# ble_lock_2020-10-10.net
KiCad netlist of a schematic drawn in Altium Designer
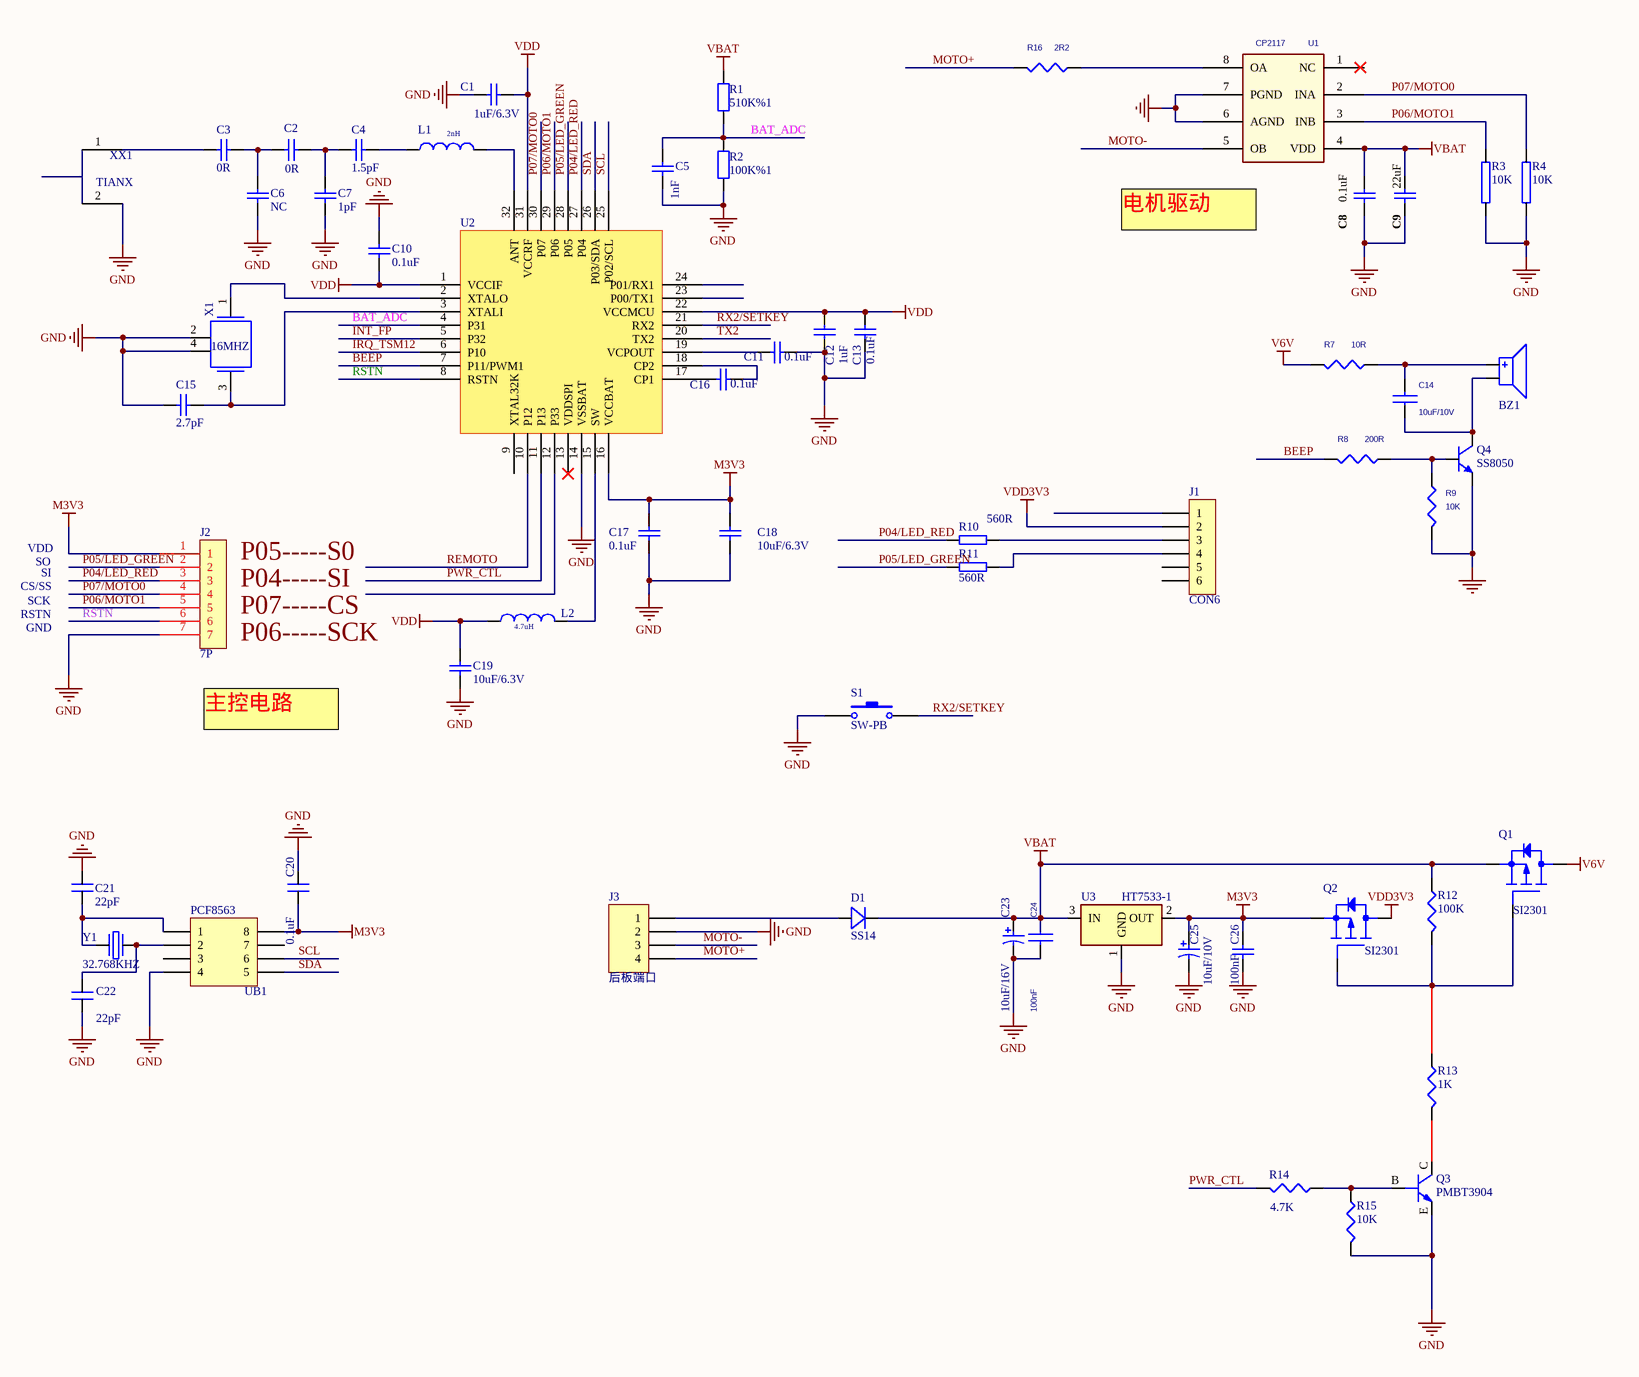
[diagram p0: ble_lock_2020-10-10.SchDoc]

(export (version "E")
  (design (tool "Eeschema 10.0.6"))
  (components
    (comp (ref "BZ1")
      (value "BUZZER")
      (footprint "BUZZER_D93_L40")
      (description "Buzzer")
      (libsource (lib "MyLibrary") (part "BUZZER"))
    )
    (comp (ref "C1")
      (value "1uF/6.3V")
      (footprint "0603C")
      (description "Capacitor")
      (fields (field (name "PUBLISHER") "Altium Limited"))
      (libsource (lib "MySchlib") (part "Cap"))
    )
    (comp (ref "C2")
      (value "0R")
      (footprint "0603C")
      (description "Capacitor")
      (fields (field (name "PUBLISHER") "Altium Limited"))
      (libsource (lib "MySchlib") (part "Cap"))
    )
    (comp (ref "C3")
      (value "0R")
      (footprint "0603C")
      (description "Capacitor")
      (fields (field (name "PUBLISHER") "Altium Limited"))
      (libsource (lib "MySchlib") (part "Cap"))
    )
    (comp (ref "C4")
      (value "1.5pF")
      (footprint "0603C")
      (description "Capacitor")
      (fields (field (name "PUBLISHER") "Altium Limited"))
      (libsource (lib "MySchlib") (part "Cap"))
    )
    (comp (ref "C5")
      (value "1nF")
      (footprint "0603C")
      (description "Capacitor, Ceramic")
      (fields (field (name "TOLERANCE") "5 %"))
      (libsource (lib "MyLibrary") (part "CAP-NP"))
    )
    (comp (ref "C6")
      (value "NC")
      (footprint "0603C")
      (description "Capacitor")
      (fields (field (name "PUBLISHER") "Altium Limited"))
      (libsource (lib "MySchlib") (part "Cap"))
    )
    (comp (ref "C7")
      (value "1pF")
      (footprint "0603C")
      (description "Capacitor")
      (fields (field (name "PUBLISHER") "Altium Limited"))
      (libsource (lib "MySchlib") (part "Cap"))
    )
    (comp (ref "C8")
      (value "0.1uF")
      (footprint "0603C")
      (description "Capacitor, Ceramic")
      (fields (field (name "TOLERANCE") "5 %"))
      (libsource (lib "MyLibrary") (part "CAP-NP"))
    )
    (comp (ref "C9")
      (value "22uF")
      (footprint "0805C")
      (description "Capacitor, Ceramic")
      (fields (field (name "TOLERANCE") "5 %"))
      (libsource (lib "MyLibrary") (part "CAP-NP"))
    )
    (comp (ref "C10")
      (value "0.1uF")
      (footprint "0603C")
      (description "Capacitor")
      (fields (field (name "PUBLISHER") "Altium Limited"))
      (libsource (lib "MySchlib") (part "Cap"))
    )
    (comp (ref "C11")
      (value "0.1uF")
      (footprint "0603C")
      (description "Capacitor")
      (fields (field (name "PUBLISHER") "Altium Limited"))
      (libsource (lib "MySchlib") (part "Cap"))
    )
    (comp (ref "C12")
      (value "1uF")
      (footprint "0603C")
      (description "Capacitor")
      (fields (field (name "PUBLISHER") "Altium Limited"))
      (libsource (lib "MySchlib") (part "Cap"))
    )
    (comp (ref "C13")
      (value "0.1uF")
      (footprint "0603C")
      (description "Capacitor")
      (fields (field (name "PUBLISHER") "Altium Limited"))
      (libsource (lib "MySchlib") (part "Cap"))
    )
    (comp (ref "C14") (value "10uF/10V") (footprint "0603C") (libsource (lib "*") (part "C_0_Dup1")))
    (comp (ref "C15")
      (value "2.7pF")
      (footprint "0603C")
      (description "Capacitor")
      (fields (field (name "PUBLISHER") "Altium Limited"))
      (libsource (lib "MySchlib") (part "Cap"))
    )
    (comp (ref "C16")
      (value "0.1uF")
      (footprint "0603C")
      (description "Capacitor")
      (fields (field (name "PUBLISHER") "Altium Limited"))
      (libsource (lib "MySchlib") (part "Cap"))
    )
    (comp (ref "C17")
      (value "0.1uF")
      (footprint "0603C")
      (description "Capacitor")
      (fields (field (name "PUBLISHER") "Altium Limited"))
      (libsource (lib "MySchlib") (part "Cap"))
    )
    (comp (ref "C18")
      (value "10uF/6.3V")
      (footprint "0603C")
      (description "Capacitor")
      (fields (field (name "PUBLISHER") "Altium Limited"))
      (libsource (lib "MySchlib") (part "Cap"))
    )
    (comp (ref "C19")
      (value "10uF/6.3V")
      (footprint "0603C")
      (description "Capacitor")
      (fields (field (name "PUBLISHER") "Altium Limited"))
      (libsource (lib "MySchlib") (part "Cap"))
    )
    (comp (ref "C20") (value "0.1uF") (footprint "0603C") (libsource (lib "自建元件库") (part "C")))
    (comp (ref "C21") (value "22pF") (footprint "0603C") (libsource (lib "自建元件库") (part "C")))
    (comp (ref "C22") (value "22pF") (footprint "0603C") (libsource (lib "自建元件库") (part "C")))
    (comp (ref "C23")
      (value "10uF/16V")
      (footprint "LC-1206_C")
      (description "Capacitor, tolerance ±20%")
      (libsource (lib "MySchLib") (part "CAP-P"))
    )
    (comp (ref "C24") (value "100nF") (footprint "0603C") (libsource (lib "*") (part "CAP NP")))
    (comp (ref "C25")
      (value "10uF/10V")
      (footprint "LC-0805_C")
      (description "Capacitor, tolerance ±20%")
      (libsource (lib "MySchLib") (part "CAP-P"))
    )
    (comp (ref "C26")
      (value "100nF")
      (footprint "0603C")
      (description "Capacitor, Ceramic")
      (fields (field (name "TOLERANCE") "5 %"))
      (libsource (lib "MyLibrary") (part "CAP-NP"))
    )
    (comp (ref "D1") (value "SS14") (footprint "LC-SMAF_S1") (libsource (lib "MySch") (part "D")))
    (comp (ref "J1")
      (value "CON6")
      (footprint "JC20-6P-H")
      (description "Connector")
      (libsource (lib "杂元件库") (part "CON6"))
    )
    (comp (ref "J2") (value "7P") (footprint "7P-2.0MM") (libsource (lib "保险箱STM32") (part "7P")))
    (comp (ref "J3")
      (value "后板端口")
      (footprint "JC20-4P-V")
      (description "Header, 4-Pin, Right Angle")
      (fields (field (name "PUBLISHER") "Altium Limited"))
      (libsource (lib "Miscellaneous Connectors") (part "Header 4H"))
    )
    (comp (ref "L1")
      (value "2nH")
      (footprint "0603L")
      (description "Power Inductor, 4.7uH, 0.7A, 260mR DCR")
      (fields
        (field (name "XMOS PART NUMBER") "E-09-0011")
        (field (name "MANUFACTURER") "Taiyo Yuden")
        (field (name "PART CREATOR") "JG")
        (field (name "APPROVED") "NO")
      )
      (libsource (lib "MySchlib") (part "INDUCTOR"))
    )
    (comp (ref "L2")
      (value "4.7uH")
      (footprint "0805L")
      (description "Power Inductor, 4.7uH, 0.7A, 260mR DCR")
      (fields
        (field (name "XMOS PART NUMBER") "E-09-0011")
        (field (name "MANUFACTURER") "Taiyo Yuden")
        (field (name "PART CREATOR") "JG")
        (field (name "APPROVED") "NO")
      )
      (libsource (lib "MySchlib") (part "INDUCTOR"))
    )
    (comp (ref "Q1")
      (value "SI2301")
      (footprint "SOT-23 - GDS")
      (libsource (lib "*") (part "PWRMOSFET_EP_DGS_0"))
    )
    (comp (ref "Q2")
      (value "SI2301")
      (footprint "SOT-23 - GDS")
      (libsource (lib "*") (part "PWRMOSFET_EP_DGS_0"))
    )
    (comp (ref "Q3") (value "PMBT3904") (footprint "SOT-23 - BCE") (libsource (lib "*") (part "PMBT3904")))
    (comp (ref "Q4")
      (value "SS8050")
      (footprint "SOT-23-3L")
      (description "Bipolar Junction Transistor")
      (libsource (lib "MyLibrary") (part "NPN_BJT"))
    )
    (comp (ref "R1")
      (value "510K%1")
      (footprint "0603R")
      (description "Resistor")
      (libsource (lib "MyLibrary") (part "Res2"))
    )
    (comp (ref "R2")
      (value "100K%1")
      (footprint "0603R")
      (description "Resistor")
      (libsource (lib "MyLibrary") (part "Res2"))
    )
    (comp (ref "R3") (value "10K") (footprint "0603R") (libsource (lib "*") (part "Pro71C3.TMP_UnNamed_1")))
    (comp (ref "R4") (value "10K") (footprint "0603R") (libsource (lib "*") (part "Pro71C3.TMP_UnNamed_1")))
    (comp (ref "R7") (value "10R") (footprint "0603R") (libsource (lib "*") (part "R_Dup1")))
    (comp (ref "R8") (value "200R") (footprint "0603R") (libsource (lib "*") (part "R_Dup1")))
    (comp (ref "R9") (value "10K") (footprint "0603R") (libsource (lib "*") (part "R_Dup1")))
    (comp (ref "R10") (value "560R") (footprint "0603R") (libsource (lib "MySch") (part "R")))
    (comp (ref "R11") (value "560R") (footprint "0603R") (libsource (lib "MySch") (part "R")))
    (comp (ref "R12") (value "100K") (footprint "LC-0603_R") (libsource (lib "*") (part "R")))
    (comp (ref "R13") (value "1K") (footprint "LC-0603_R") (libsource (lib "*") (part "R")))
    (comp (ref "R14") (value "4.7K") (footprint "LC-0603_R") (libsource (lib "*") (part "R")))
    (comp (ref "R15") (value "10K") (footprint "LC-0603_R") (libsource (lib "*") (part "R")))
    (comp (ref "R16") (value "2R2") (footprint "0603R") (libsource (lib "*") (part "R_Dup1")))
    (comp (ref "S1")
      (value "SW-PB")
      (footprint "6*6H9")
      (description "Switch")
      (fields (field (name "PUBLISHER") "Altium Limited"))
      (libsource (lib "Miscellaneous Devices") (part "SW-PB"))
    )
    (comp (ref "U1") (value "CP2117") (footprint "SOP8") (libsource (lib "*") (part "AM24LC02_0")))
    (comp (ref "U2")
      (value "BK3431Q")
      (footprint "QFN32_4*4*0.4")
      (libsource (lib "BK3431") (part "BK3431Q"))
    )
    (comp (ref "U3") (value "HT7533-1") (footprint "SOT-23-3L") (libsource (lib "*") (part "XC6206P302M")))
    (comp (ref "UB1") (value "PCF8563") (footprint "SOP8") (libsource (lib "MySch") (part "IC8")))
    (comp (ref "X1")
      (value "16MHZ")
      (footprint "XTAL3225")
      (fields
        (field (name "XMOS PART NUMBER") "E-07-0030")
        (field (name "MANUFACTURER") "Abracon")
        (field (name "MANUFACTURER PART NUMBER") "ABLS-24.000MHz-B4")
        (field (name "PART CREATOR") "JG")
        (field (name "APPROVED") "NO")
      )
      (libsource (lib "MySchlib") (part "OSC"))
    )
    (comp (ref "XX1")
      (value "TIANX")
      (footprint "BT_NAMI_NO")
      (libsource (lib "885阿里云PCB_Project1") (part "TIANX"))
    )
    (comp (ref "Y1") (value "32.768KHZ") (footprint "晶振-9") (libsource (lib "MySch") (part "晶振")))
  )
  (nets
    (net (code "1") (name "/BAT_ADC") (class "Default")
      (node (ref "C5") (pin "2") (pinfunction "2_2") (pintype "passive"))
      (node (ref "R1") (pin "2") (pinfunction "2_2") (pintype "passive"))
      (node (ref "R2") (pin "1") (pinfunction "1_1") (pintype "passive"))
      (node (ref "U2") (pin "4") (pinfunction "P31_4") (pintype "passive"))
    )
    (net (code "2") (name "/BEEP") (class "Default")
      (node (ref "R8") (pin "2") (pinfunction "2_2") (pintype "passive"))
      (node (ref "U2") (pin "7") (pinfunction "P11/PWM1_7") (pintype "passive"))
    )
    (net (code "3") (name "/INT_FP") (class "Default")
      (node (ref "U2") (pin "5") (pinfunction "P32_5") (pintype "passive"))
    )
    (net (code "4") (name "/IRQ_TSM12") (class "Default")
      (node (ref "U2") (pin "6") (pinfunction "P10_6") (pintype "passive"))
    )
    (net (code "5") (name "/MOTO+") (class "Default")
      (node (ref "J3") (pin "4") (pinfunction "4_4") (pintype "passive"))
      (node (ref "R16") (pin "2") (pinfunction "2_2") (pintype "passive"))
    )
    (net (code "6") (name "/MOTO-") (class "Default")
      (node (ref "J3") (pin "3") (pinfunction "3_3") (pintype "passive"))
      (node (ref "U1") (pin "5") (pinfunction "OB_5") (pintype "passive"))
    )
    (net (code "7") (name "/P04{slash}LED_RED") (class "Default")
      (node (ref "J2") (pin "3") (pinfunction "3_3") (pintype "passive"))
      (node (ref "R10") (pin "1") (pintype "passive"))
      (node (ref "U2") (pin "27") (pinfunction "P04_27") (pintype "passive"))
    )
    (net (code "8") (name "/P05{slash}LED_GREEN") (class "Default")
      (node (ref "J2") (pin "2") (pinfunction "2_2") (pintype "passive"))
      (node (ref "R11") (pin "1") (pintype "passive"))
      (node (ref "U2") (pin "28") (pinfunction "P05_28") (pintype "passive"))
    )
    (net (code "9") (name "/P06{slash}MOTO1") (class "Default")
      (node (ref "J2") (pin "5") (pinfunction "5_5") (pintype "passive"))
      (node (ref "R3") (pin "2") (pintype "passive"))
      (node (ref "U1") (pin "3") (pinfunction "INB_3") (pintype "passive"))
      (node (ref "U2") (pin "29") (pinfunction "P06_29") (pintype "passive"))
    )
    (net (code "10") (name "/P07{slash}MOTO0") (class "Default")
      (node (ref "J2") (pin "4") (pinfunction "4_4") (pintype "passive"))
      (node (ref "R4") (pin "2") (pintype "passive"))
      (node (ref "U1") (pin "2") (pinfunction "INA_2") (pintype "passive"))
      (node (ref "U2") (pin "30") (pinfunction "P07_30") (pintype "passive"))
    )
    (net (code "11") (name "/PWR_CTL") (class "Default")
      (node (ref "R14") (pin "2") (pinfunction "2_2") (pintype "passive"))
      (node (ref "U2") (pin "11") (pinfunction "P13_11") (pintype "passive"))
    )
    (net (code "12") (name "/REMOTO") (class "Default")
      (node (ref "U2") (pin "10") (pinfunction "P12_10") (pintype "passive"))
    )
    (net (code "13") (name "/RSTN") (class "Default")
      (node (ref "J2") (pin "6") (pinfunction "6_6") (pintype "passive"))
      (node (ref "U2") (pin "8") (pinfunction "RSTN_8") (pintype "passive"))
    )
    (net (code "14") (name "/RX2{slash}SETKEY") (class "Default")
      (node (ref "S1") (pin "2") (pinfunction "2_2") (pintype "passive"))
      (node (ref "U2") (pin "21") (pinfunction "RX2_21") (pintype "passive"))
    )
    (net (code "15") (name "/SCL") (class "Default")
      (node (ref "U2") (pin "25") (pinfunction "P02/SCL_25") (pintype "passive"))
      (node (ref "UB1") (pin "6") (pinfunction "6_6") (pintype "passive"))
    )
    (net (code "16") (name "/SDA") (class "Default")
      (node (ref "U2") (pin "26") (pinfunction "P03/SDA_26") (pintype "passive"))
      (node (ref "UB1") (pin "5") (pinfunction "5_5") (pintype "passive"))
    )
    (net (code "17") (name "/TX2") (class "Default")
      (node (ref "U2") (pin "20") (pinfunction "TX2_20") (pintype "passive"))
    )
    (net (code "18") (name "GND") (class "Default")
      (node (ref "C1") (pin "1") (pinfunction "1_1") (pintype "passive"))
      (node (ref "C10") (pin "1") (pinfunction "1_1") (pintype "passive"))
      (node (ref "C11") (pin "2") (pinfunction "2_2") (pintype "passive"))
      (node (ref "C12") (pin "1") (pinfunction "1_1") (pintype "passive"))
      (node (ref "C13") (pin "1") (pinfunction "1_1") (pintype "passive"))
      (node (ref "C15") (pin "1") (pinfunction "1_1") (pintype "passive"))
      (node (ref "C17") (pin "2") (pinfunction "2_2") (pintype "passive"))
      (node (ref "C18") (pin "2") (pinfunction "2_2") (pintype "passive"))
      (node (ref "C19") (pin "1") (pinfunction "1_1") (pintype "passive"))
      (node (ref "C20") (pin "2") (pintype "passive"))
      (node (ref "C21") (pin "2") (pintype "passive"))
      (node (ref "C22") (pin "1") (pintype "passive"))
      (node (ref "C23") (pin "2") (pinfunction "2_2") (pintype "passive"))
      (node (ref "C24") (pin "2") (pinfunction "2_2") (pintype "passive"))
      (node (ref "C25") (pin "2") (pinfunction "2_2") (pintype "passive"))
      (node (ref "C26") (pin "2") (pinfunction "2_2") (pintype "passive"))
      (node (ref "C5") (pin "1") (pinfunction "1_1") (pintype "passive"))
      (node (ref "C6") (pin "2") (pinfunction "2_2") (pintype "passive"))
      (node (ref "C7") (pin "1") (pinfunction "1_1") (pintype "passive"))
      (node (ref "C8") (pin "2") (pinfunction "2_2") (pintype "passive"))
      (node (ref "C9") (pin "2") (pinfunction "2_2") (pintype "passive"))
      (node (ref "J2") (pin "7") (pinfunction "7_7") (pintype "passive"))
      (node (ref "J3") (pin "2") (pinfunction "2_2") (pintype "passive"))
      (node (ref "Q3") (pin "E") (pinfunction "EMITTER_E") (pintype "passive"))
      (node (ref "Q4") (pin "2") (pinfunction "2_2") (pintype "passive"))
      (node (ref "R15") (pin "2") (pinfunction "2_2") (pintype "passive"))
      (node (ref "R2") (pin "2") (pinfunction "2_2") (pintype "passive"))
      (node (ref "R3") (pin "1") (pintype "passive"))
      (node (ref "R4") (pin "1") (pintype "passive"))
      (node (ref "R9") (pin "2") (pinfunction "2_2") (pintype "passive"))
      (node (ref "S1") (pin "1") (pinfunction "1_1") (pintype "passive"))
      (node (ref "U1") (pin "6") (pinfunction "AGND_6") (pintype "passive"))
      (node (ref "U1") (pin "7") (pinfunction "PGND_7") (pintype "passive"))
      (node (ref "U2") (pin "14") (pinfunction "VSSBAT_14") (pintype "passive"))
      (node (ref "U3") (pin "1") (pinfunction "GND_1") (pintype "passive"))
      (node (ref "UB1") (pin "4") (pinfunction "4_4") (pintype "passive"))
      (node (ref "X1") (pin "2") (pintype "passive"))
      (node (ref "X1") (pin "4") (pintype "passive"))
      (node (ref "XX1") (pin "2") (pinfunction "2_2") (pintype "passive"))
    )
    (net (code "19") (name "M3V3") (class "Default")
      (node (ref "C17") (pin "1") (pinfunction "1_1") (pintype "passive"))
      (node (ref "C18") (pin "1") (pinfunction "1_1") (pintype "passive"))
      (node (ref "C20") (pin "1") (pintype "passive"))
      (node (ref "C25") (pin "1") (pinfunction "1_1") (pintype "passive"))
      (node (ref "C26") (pin "1") (pinfunction "1_1") (pintype "passive"))
      (node (ref "J2") (pin "1") (pinfunction "1_1") (pintype "passive"))
      (node (ref "Q2") (pin "S") (pinfunction "SOURCE_S") (pintype "passive"))
      (node (ref "U2") (pin "16") (pinfunction "VCCBAT_16") (pintype "passive"))
      (node (ref "U3") (pin "2") (pinfunction "OUT_2") (pintype "passive"))
      (node (ref "UB1") (pin "8") (pinfunction "8_8") (pintype "passive"))
    )
    (net (code "20") (name "Net-(BZ1-Pad1)") (class "Default")
      (node (ref "BZ1") (pin "1") (pintype "passive"))
      (node (ref "C14") (pin "2") (pinfunction "2_2") (pintype "passive"))
      (node (ref "R7") (pin "1") (pinfunction "1_1") (pintype "passive"))
    )
    (net (code "21") (name "Net-(BZ1-Pad2)") (class "Default")
      (node (ref "BZ1") (pin "2") (pintype "passive"))
      (node (ref "C14") (pin "1") (pinfunction "1_1") (pintype "passive"))
      (node (ref "Q4") (pin "3") (pinfunction "3_3") (pintype "passive"))
    )
    (net (code "22") (name "Net-(C2-Pad1)") (class "Default")
      (node (ref "C2") (pin "1") (pinfunction "1_1") (pintype "passive"))
      (node (ref "C3") (pin "2") (pinfunction "2_2") (pintype "passive"))
      (node (ref "C6") (pin "1") (pinfunction "1_1") (pintype "passive"))
    )
    (net (code "23") (name "Net-(C2-Pad2)") (class "Default")
      (node (ref "C2") (pin "2") (pinfunction "2_2") (pintype "passive"))
      (node (ref "C4") (pin "2") (pinfunction "2_2") (pintype "passive"))
      (node (ref "C7") (pin "2") (pinfunction "2_2") (pintype "passive"))
    )
    (net (code "24") (name "Net-(C3-Pad1)") (class "Default")
      (node (ref "C3") (pin "1") (pinfunction "1_1") (pintype "passive"))
      (node (ref "XX1") (pin "1") (pinfunction "1_1") (pintype "passive"))
    )
    (net (code "25") (name "Net-(C21-Pad1)") (class "Default")
      (node (ref "C21") (pin "1") (pintype "passive"))
      (node (ref "UB1") (pin "1") (pinfunction "1_1") (pintype "passive"))
      (node (ref "Y1") (pin "2") (pintype "passive"))
    )
    (net (code "26") (name "Net-(C22-Pad2)") (class "Default")
      (node (ref "C22") (pin "2") (pintype "passive"))
      (node (ref "UB1") (pin "2") (pinfunction "2_2") (pintype "passive"))
      (node (ref "Y1") (pin "1") (pintype "passive"))
    )
    (net (code "27") (name "Net-(D1-A)") (class "Default")
      (node (ref "D1") (pin "1") (pinfunction "A_1") (pintype "passive"))
      (node (ref "J3") (pin "1") (pinfunction "1_1") (pintype "passive"))
    )
    (net (code "28") (name "Net-(J1-Pad3)") (class "Default")
      (node (ref "J1") (pin "3") (pinfunction "3_3") (pintype "passive"))
      (node (ref "R10") (pin "2") (pintype "passive"))
    )
    (net (code "29") (name "Net-(J1-Pad4)") (class "Default")
      (node (ref "J1") (pin "4") (pinfunction "4_4") (pintype "passive"))
      (node (ref "R11") (pin "2") (pintype "passive"))
    )
    (net (code "30") (name "Net-(L1-P1)") (class "Default")
      (node (ref "C4") (pin "1") (pinfunction "1_1") (pintype "passive"))
      (node (ref "L1") (pin "1") (pinfunction "P1_1") (pintype "passive"))
    )
    (net (code "31") (name "Net-(L1-P2)") (class "Default")
      (node (ref "L1") (pin "2") (pinfunction "P2_2") (pintype "passive"))
      (node (ref "U2") (pin "32") (pinfunction "ANT_32") (pintype "passive"))
    )
    (net (code "32") (name "Net-(L2-P2)") (class "Default")
      (node (ref "L2") (pin "2") (pinfunction "P2_2") (pintype "passive"))
      (node (ref "U2") (pin "15") (pinfunction "SW_15") (pintype "passive"))
    )
    (net (code "33") (name "Net-(Q1-GATE)") (class "Default")
      (node (ref "Q1") (pin "G") (pinfunction "GATE_G") (pintype "passive"))
      (node (ref "Q2") (pin "G") (pinfunction "GATE_G") (pintype "passive"))
      (node (ref "R12") (pin "2") (pinfunction "2_2") (pintype "passive"))
      (node (ref "R13") (pin "1") (pinfunction "1_1") (pintype "passive"))
    )
    (net (code "34") (name "Net-(Q3-BASE)") (class "Default")
      (node (ref "Q3") (pin "B") (pinfunction "BASE_B") (pintype "passive"))
      (node (ref "R14") (pin "1") (pinfunction "1_1") (pintype "passive"))
      (node (ref "R15") (pin "1") (pinfunction "1_1") (pintype "passive"))
    )
    (net (code "35") (name "Net-(Q3-COLLECTOR)") (class "Default")
      (node (ref "Q3") (pin "C") (pinfunction "COLLECTOR_C") (pintype "passive"))
      (node (ref "R13") (pin "2") (pinfunction "2_2") (pintype "passive"))
    )
    (net (code "36") (name "Net-(Q4-Pad1)") (class "Default")
      (node (ref "Q4") (pin "1") (pinfunction "1_1") (pintype "passive"))
      (node (ref "R8") (pin "1") (pinfunction "1_1") (pintype "passive"))
      (node (ref "R9") (pin "1") (pinfunction "1_1") (pintype "passive"))
    )
    (net (code "37") (name "Net-(U1-OA)") (class "Default")
      (node (ref "R16") (pin "1") (pinfunction "1_1") (pintype "passive"))
      (node (ref "U1") (pin "8") (pinfunction "OA_8") (pintype "passive"))
    )
    (net (code "38") (name "Net-(U2-CP1)") (class "Default")
      (node (ref "C16") (pin "1") (pinfunction "1_1") (pintype "passive"))
      (node (ref "U2") (pin "17") (pinfunction "CP1_17") (pintype "passive"))
    )
    (net (code "39") (name "Net-(U2-CP2)") (class "Default")
      (node (ref "C16") (pin "2") (pinfunction "2_2") (pintype "passive"))
      (node (ref "U2") (pin "18") (pinfunction "CP2_18") (pintype "passive"))
    )
    (net (code "40") (name "Net-(U2-VCPOUT)") (class "Default")
      (node (ref "C11") (pin "1") (pinfunction "1_1") (pintype "passive"))
      (node (ref "U2") (pin "19") (pinfunction "VCPOUT_19") (pintype "passive"))
    )
    (net (code "41") (name "Net-(U2-XTALI)") (class "Default")
      (node (ref "C15") (pin "2") (pinfunction "2_2") (pintype "passive"))
      (node (ref "U2") (pin "3") (pinfunction "XTALI_3") (pintype "passive"))
      (node (ref "X1") (pin "3") (pintype "passive"))
    )
    (net (code "42") (name "Net-(U2-XTALO)") (class "Default")
      (node (ref "U2") (pin "2") (pinfunction "XTALO_2") (pintype "passive"))
      (node (ref "X1") (pin "1") (pintype "passive"))
    )
    (net (code "43") (name "V6V") (class "Default")
      (node (ref "Q1") (pin "D") (pinfunction "DRAIN_D") (pintype "passive"))
      (node (ref "R7") (pin "2") (pinfunction "2_2") (pintype "passive"))
    )
    (net (code "44") (name "VBAT") (class "Default")
      (node (ref "C23") (pin "1") (pinfunction "1_1") (pintype "passive"))
      (node (ref "C24") (pin "1") (pinfunction "1_1") (pintype "passive"))
      (node (ref "C8") (pin "1") (pinfunction "1_1") (pintype "passive"))
      (node (ref "C9") (pin "1") (pinfunction "1_1") (pintype "passive"))
      (node (ref "D1") (pin "2") (pinfunction "K_2") (pintype "passive"))
      (node (ref "Q1") (pin "S") (pinfunction "SOURCE_S") (pintype "passive"))
      (node (ref "R1") (pin "1") (pinfunction "1_1") (pintype "passive"))
      (node (ref "R12") (pin "1") (pinfunction "1_1") (pintype "passive"))
      (node (ref "U1") (pin "4") (pinfunction "VDD_4") (pintype "passive"))
      (node (ref "U3") (pin "3") (pinfunction "IN_3") (pintype "passive"))
    )
    (net (code "45") (name "VDD") (class "Default")
      (node (ref "C1") (pin "2") (pinfunction "2_2") (pintype "passive"))
      (node (ref "C10") (pin "2") (pinfunction "2_2") (pintype "passive"))
      (node (ref "C12") (pin "2") (pinfunction "2_2") (pintype "passive"))
      (node (ref "C13") (pin "2") (pinfunction "2_2") (pintype "passive"))
      (node (ref "C19") (pin "2") (pinfunction "2_2") (pintype "passive"))
      (node (ref "L2") (pin "1") (pinfunction "P1_1") (pintype "passive"))
      (node (ref "U2") (pin "1") (pinfunction "VCCIF_1") (pintype "passive"))
      (node (ref "U2") (pin "22") (pinfunction "VCCMCU_22") (pintype "passive"))
      (node (ref "U2") (pin "31") (pinfunction "VCCRF_31") (pintype "passive"))
    )
    (net (code "46") (name "VDD3V3") (class "Default")
      (node (ref "J1") (pin "2") (pinfunction "2_2") (pintype "passive"))
      (node (ref "Q2") (pin "D") (pinfunction "DRAIN_D") (pintype "passive"))
    )
    (net (code "47") (name "unconnected-(J1-Pad1)") (class "Default")
      (node (ref "J1") (pin "1") (pinfunction "1_1") (pintype "passive"))
    )
    (net (code "48") (name "unconnected-(J1-Pad5)") (class "Default")
      (node (ref "J1") (pin "5") (pinfunction "5_5") (pintype "passive"))
    )
    (net (code "49") (name "unconnected-(J1-Pad6)") (class "Default")
      (node (ref "J1") (pin "6") (pinfunction "6_6") (pintype "passive"))
    )
    (net (code "50") (name "unconnected-(U1-NC-Pad1)") (class "Default")
      (node (ref "U1") (pin "1") (pinfunction "NC_1") (pintype "passive"))
    )
    (net (code "51") (name "unconnected-(U2-P00{slash}TX1-Pad23)") (class "Default")
      (node (ref "U2") (pin "23") (pinfunction "P00/TX1_23") (pintype "passive"))
    )
    (net (code "52") (name "unconnected-(U2-P01{slash}RX1-Pad24)") (class "Default")
      (node (ref "U2") (pin "24") (pinfunction "P01/RX1_24") (pintype "passive"))
    )
    (net (code "53") (name "unconnected-(U2-P33-Pad12)") (class "Default")
      (node (ref "U2") (pin "12") (pinfunction "P33_12") (pintype "passive"))
    )
    (net (code "54") (name "unconnected-(U2-VDDSPI-Pad13)") (class "Default")
      (node (ref "U2") (pin "13") (pinfunction "VDDSPI_13") (pintype "passive+no_connect"))
    )
    (net (code "55") (name "unconnected-(U2-XTAL32K-Pad9)") (class "Default")
      (node (ref "U2") (pin "9") (pinfunction "XTAL32K_9") (pintype "passive"))
    )
    (net (code "56") (name "unconnected-(UB1-Pad3)") (class "Default")
      (node (ref "UB1") (pin "3") (pinfunction "3_3") (pintype "passive"))
    )
    (net (code "57") (name "unconnected-(UB1-Pad7)") (class "Default")
      (node (ref "UB1") (pin "7") (pinfunction "7_7") (pintype "passive"))
    )
  )
)
